# Power.net
KiCad netlist of a schematic drawn in Altium Designer
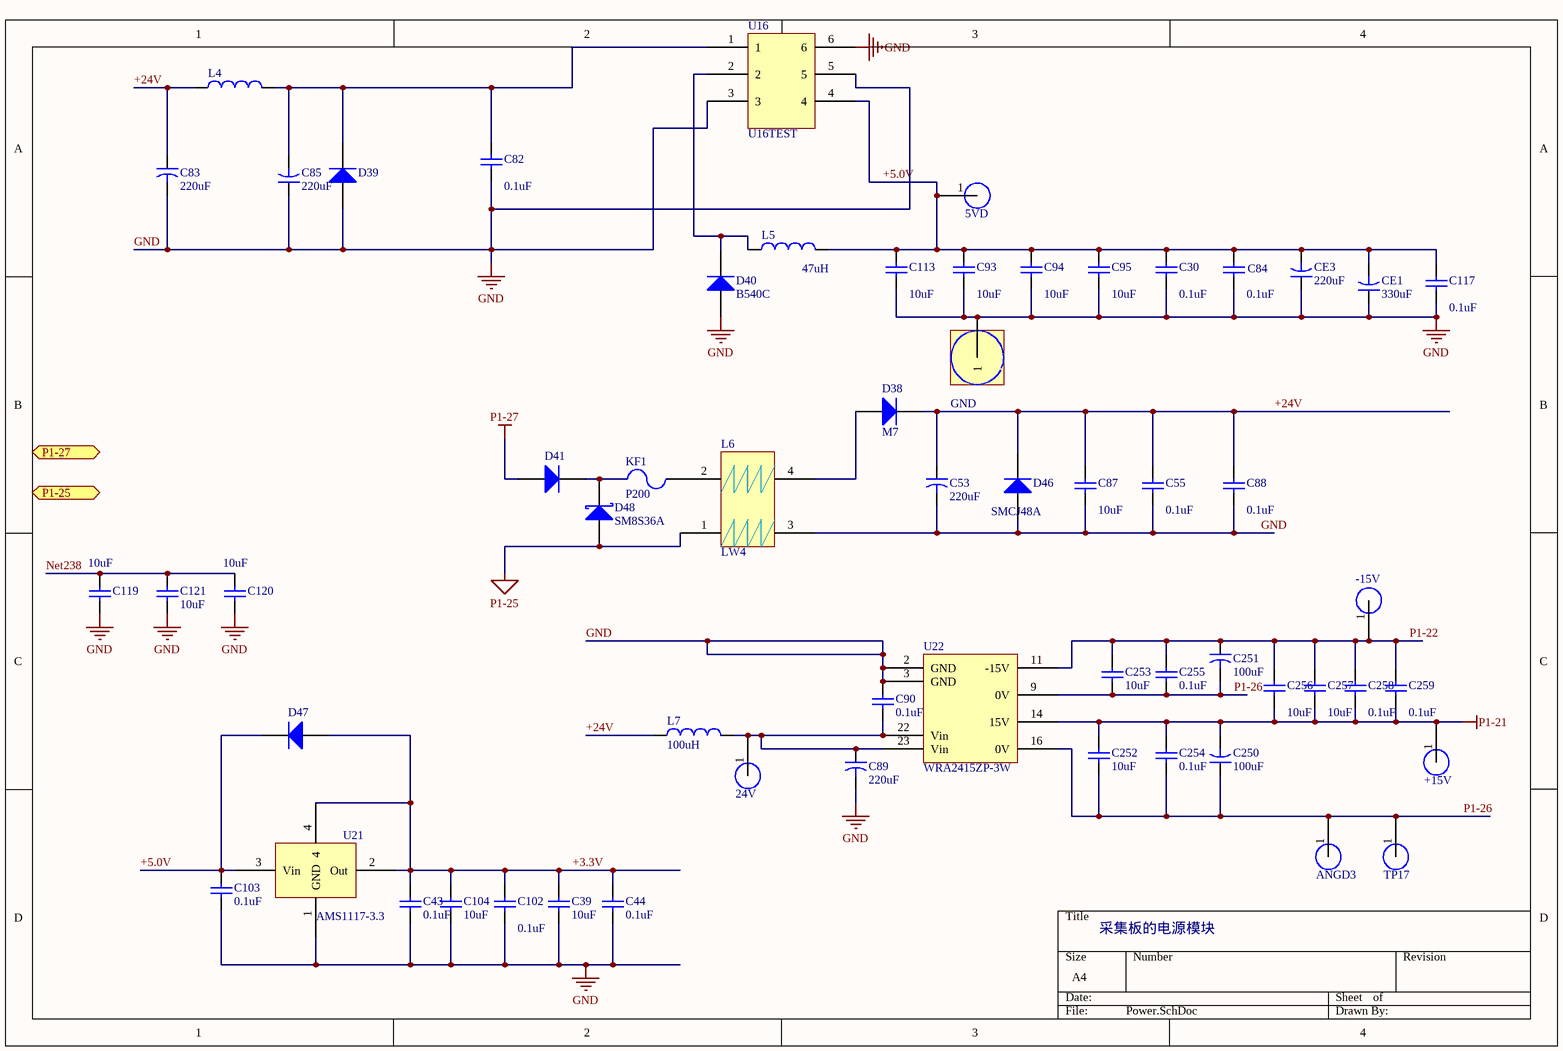
[diagram p0: Power.SchDoc]

(export (version "E")
  (design (tool "Eeschema 10.0.6"))
  (components
    (comp (ref "+15V") (value "PIN") (footprint "圆形焊盘") (libsource (lib "圆孔") (part "Component_1")))
    (comp (ref "-15V") (value "PIN") (footprint "圆形焊盘") (libsource (lib "圆孔") (part "Component_1")))
    (comp (ref "5VD") (value "PIN") (footprint "圆形焊盘") (libsource (lib "") (part "Component_1_1")))
    (comp (ref "24V") (value "PIN") (footprint "圆形焊盘") (libsource (lib "圆孔") (part "Component_1")))
    (comp (ref "ANGD3") (value "PIN") (footprint "圆形焊盘") (libsource (lib "圆孔") (part "Component_1")))
    (comp (ref "C30")
      (value "0.1uF")
      (footprint "采集板3.0增加1路模拟量2:C0805")
      (description "Capacitor")
      (fields (field (name "Comment") "104/10%") (field (name "PUBLISHER") "Altium Limited"))
      (libsource (lib "Miscellaneous Devices") (part "Cap"))
    )
    (comp (ref "C39")
      (value "10uF")
      (footprint "C1206")
      (description "Capacitor")
      (fields (field (name "Comment") "Cap") (field (name "PUBLISHER") "Altium Limited"))
      (libsource (lib "Miscellaneous Devices") (part "Cap"))
    )
    (comp (ref "C43")
      (value "0.1uF")
      (footprint "采集板3.0增加1路模拟量2:C0805")
      (description "Capacitor")
      (fields (field (name "Comment") "104/10%") (field (name "PUBLISHER") "Altium Limited"))
      (libsource (lib "Miscellaneous Devices") (part "Cap"))
    )
    (comp (ref "C44")
      (value "0.1uF")
      (footprint "采集板3.0增加1路模拟量2:C0805")
      (description "Capacitor")
      (fields (field (name "Comment") "Cap") (field (name "PUBLISHER") "Altium Limited"))
      (libsource (lib "Miscellaneous Devices") (part "Cap"))
    )
    (comp (ref "C53")
      (value "220uF")
      (footprint "采集板3.0增加1路模拟量2:8*12")
      (description "Capacitor")
      (fields (field (name "Comment") "Cap2") (field (name "PUBLISHER") "Altium Limited"))
      (libsource (lib "") (part "Cap2_1"))
    )
    (comp (ref "C55")
      (value "0.1uF")
      (footprint "采集板3.0增加1路模拟量2:C0805")
      (description "Capacitor")
      (fields (field (name "Comment") "104/10%") (field (name "PUBLISHER") "Altium Limited"))
      (libsource (lib "Miscellaneous Devices") (part "Cap"))
    )
    (comp (ref "C82")
      (value "0.1uF")
      (footprint "采集板3.0增加1路模拟量2:C0805")
      (description "Capacitor")
      (fields (field (name "Comment") "22pF/5%") (field (name "PUBLISHER") "Altium Limited"))
      (libsource (lib "Miscellaneous Devices") (part "Cap"))
    )
    (comp (ref "C83")
      (value "220uF")
      (footprint "采集板3.0增加1路模拟量2:8*12")
      (description "Capacitor")
      (fields (field (name "Comment") "Cap2") (field (name "PUBLISHER") "Altium Limited"))
      (libsource (lib "") (part "Cap2_1"))
    )
    (comp (ref "C84")
      (value "0.1uF")
      (footprint "采集板3.0增加1路模拟量2:C0805")
      (description "Capacitor")
      (fields (field (name "Comment") "104/10%") (field (name "PUBLISHER") "Altium Limited"))
      (libsource (lib "Miscellaneous Devices") (part "Cap"))
    )
    (comp (ref "C85")
      (value "220uF")
      (footprint "采集板3.0增加1路模拟量2:8*12")
      (description "Capacitor")
      (fields (field (name "Comment") "Cap2") (field (name "PUBLISHER") "Altium Limited"))
      (libsource (lib "Miscellaneous Devices") (part "Cap2"))
    )
    (comp (ref "C87")
      (value "10uF")
      (footprint "C1206")
      (description "Capacitor")
      (fields (field (name "PUBLISHER") "Altium Limited"))
      (libsource (lib "Miscellaneous Devices") (part "Cap"))
    )
    (comp (ref "C88")
      (value "0.1uF")
      (footprint "采集板3.0增加1路模拟量2:C0805")
      (description "Capacitor")
      (fields (field (name "Comment") "104/10%") (field (name "PUBLISHER") "Altium Limited"))
      (libsource (lib "Miscellaneous Devices") (part "Cap"))
    )
    (comp (ref "C89")
      (value "220uF")
      (footprint "采集板3.0增加1路模拟量2:8*12")
      (description "Capacitor")
      (fields (field (name "Comment") "Cap2") (field (name "PUBLISHER") "Altium Limited"))
      (libsource (lib "") (part "Cap2_1"))
    )
    (comp (ref "C90")
      (value "0.1uF")
      (footprint "采集板3.0增加1路模拟量2:C0805")
      (description "Capacitor")
      (fields (field (name "Comment") "104/10%") (field (name "PUBLISHER") "Altium Limited"))
      (libsource (lib "Miscellaneous Devices") (part "Cap"))
    )
    (comp (ref "C93")
      (value "10uF")
      (footprint "C1206")
      (description "Capacitor")
      (fields (field (name "PUBLISHER") "Altium Limited"))
      (libsource (lib "Miscellaneous Devices") (part "Cap"))
    )
    (comp (ref "C94")
      (value "10uF")
      (footprint "C1206")
      (description "Capacitor")
      (fields (field (name "PUBLISHER") "Altium Limited"))
      (libsource (lib "Miscellaneous Devices") (part "Cap"))
    )
    (comp (ref "C95")
      (value "10uF")
      (footprint "C1206")
      (description "Capacitor")
      (fields (field (name "PUBLISHER") "Altium Limited"))
      (libsource (lib "Miscellaneous Devices") (part "Cap"))
    )
    (comp (ref "C102")
      (value "0.1uF")
      (footprint "采集板3.0增加1路模拟量2:C0805")
      (description "Capacitor")
      (fields (field (name "Comment") "Cap") (field (name "PUBLISHER") "Altium Limited"))
      (libsource (lib "Miscellaneous Devices") (part "Cap"))
    )
    (comp (ref "C103")
      (value "0.1uF")
      (footprint "采集板3.0增加1路模拟量2:C0805")
      (description "Capacitor")
      (fields (field (name "Comment") "104/10%") (field (name "PUBLISHER") "Altium Limited"))
      (libsource (lib "Miscellaneous Devices") (part "Cap"))
    )
    (comp (ref "C104")
      (value "10uF")
      (footprint "C1206")
      (description "Capacitor")
      (fields (field (name "Comment") "Cap") (field (name "PUBLISHER") "Altium Limited"))
      (libsource (lib "Miscellaneous Devices") (part "Cap"))
    )
    (comp (ref "C113")
      (value "10uF")
      (footprint "C1206")
      (description "Capacitor")
      (fields (field (name "Comment") "Cap") (field (name "PUBLISHER") "Altium Limited"))
      (libsource (lib "Miscellaneous Devices") (part "Cap"))
    )
    (comp (ref "C117")
      (value "0.1uF")
      (footprint "采集板3.0增加1路模拟量2:C0805")
      (description "Capacitor")
      (fields (field (name "Comment") "Cap") (field (name "PUBLISHER") "Altium Limited"))
      (libsource (lib "Miscellaneous Devices") (part "Cap"))
    )
    (comp (ref "C119")
      (value "10uF")
      (footprint "C1210")
      (description "Capacitor")
      (fields (field (name "Comment") "Cap") (field (name "PUBLISHER") "Altium Limited"))
      (libsource (lib "Miscellaneous Devices") (part "Cap"))
    )
    (comp (ref "C120")
      (value "10uF")
      (footprint "C1210")
      (description "Capacitor")
      (fields (field (name "Comment") "Cap") (field (name "PUBLISHER") "Altium Limited"))
      (libsource (lib "Miscellaneous Devices") (part "Cap"))
    )
    (comp (ref "C121")
      (value "10uF")
      (footprint "C1210")
      (description "Capacitor")
      (fields (field (name "Comment") "Cap") (field (name "PUBLISHER") "Altium Limited"))
      (libsource (lib "Miscellaneous Devices") (part "Cap"))
    )
    (comp (ref "C250")
      (value "100uF")
      (footprint "采集板3.0增加1路模拟量2:8*12")
      (description "Capacitor")
      (fields (field (name "Comment") "Cap2") (field (name "PUBLISHER") "Altium Limited"))
      (libsource (lib "Miscellaneous Devices") (part "Cap2"))
    )
    (comp (ref "C251")
      (value "100uF")
      (footprint "采集板3.0增加1路模拟量2:8*12")
      (description "Capacitor")
      (fields (field (name "Comment") "Cap2") (field (name "PUBLISHER") "Altium Limited"))
      (libsource (lib "Miscellaneous Devices") (part "Cap2"))
    )
    (comp (ref "C252")
      (value "10uF")
      (footprint "C1206")
      (description "Capacitor")
      (fields (field (name "PUBLISHER") "Altium Limited"))
      (libsource (lib "Miscellaneous Devices") (part "Cap"))
    )
    (comp (ref "C253")
      (value "10uF")
      (footprint "C1206")
      (description "Capacitor")
      (fields (field (name "PUBLISHER") "Altium Limited"))
      (libsource (lib "Miscellaneous Devices") (part "Cap"))
    )
    (comp (ref "C254")
      (value "0.1uF")
      (footprint "采集板3.0增加1路模拟量2:C0805")
      (description "Capacitor")
      (fields (field (name "Comment") "104/10%") (field (name "PUBLISHER") "Altium Limited"))
      (libsource (lib "Miscellaneous Devices") (part "Cap"))
    )
    (comp (ref "C255")
      (value "0.1uF")
      (footprint "采集板3.0增加1路模拟量2:C0805")
      (description "Capacitor")
      (fields (field (name "Comment") "104/10%") (field (name "PUBLISHER") "Altium Limited"))
      (libsource (lib "Miscellaneous Devices") (part "Cap"))
    )
    (comp (ref "C256")
      (value "10uF")
      (footprint "C1206")
      (description "Capacitor")
      (fields (field (name "PUBLISHER") "Altium Limited"))
      (libsource (lib "Miscellaneous Devices") (part "Cap"))
    )
    (comp (ref "C257")
      (value "10uF")
      (footprint "C1206")
      (description "Capacitor")
      (fields (field (name "PUBLISHER") "Altium Limited"))
      (libsource (lib "Miscellaneous Devices") (part "Cap"))
    )
    (comp (ref "C258")
      (value "0.1uF")
      (footprint "采集板3.0增加1路模拟量2:C0805")
      (description "Capacitor")
      (fields (field (name "Comment") "104/10%") (field (name "PUBLISHER") "Altium Limited"))
      (libsource (lib "Miscellaneous Devices") (part "Cap"))
    )
    (comp (ref "C259")
      (value "0.1uF")
      (footprint "采集板3.0增加1路模拟量2:C0805")
      (description "Capacitor")
      (fields (field (name "Comment") "104/10%") (field (name "PUBLISHER") "Altium Limited"))
      (libsource (lib "Miscellaneous Devices") (part "Cap"))
    )
    (comp (ref "CE1")
      (value "330uF")
      (footprint "采集板3.0增加1路模拟量2:8*12")
      (description "Capacitor")
      (fields (field (name "Comment") "Cap2") (field (name "PUBLISHER") "Altium Limited"))
      (libsource (lib "Miscellaneous Devices") (part "Cap2"))
    )
    (comp (ref "CE3")
      (value "220uF")
      (footprint "采集板3.0增加1路模拟量2:8*12")
      (description "Capacitor")
      (fields (field (name "Comment") "Cap2") (field (name "PUBLISHER") "Altium Limited"))
      (libsource (lib "Miscellaneous Devices") (part "Cap2"))
    )
    (comp (ref "D38")
      (value "M7")
      (footprint "DO214AB")
      (description "1 Amp General Purpose Rectifier")
      (fields (field (name "PUBLISHER") "Altium Limited"))
      (libsource (lib "Miscellaneous Devices") (part "Diode 1N4007"))
    )
    (comp (ref "D39")
      (value "SMCJ48A")
      (footprint "DO214AB")
      (description "Default Diode")
      (fields (field (name "PUBLISHER") "Altium Limited"))
      (libsource (lib "Miscellaneous Devices") (part "Diode"))
    )
    (comp (ref "D40")
      (value "B540C")
      (footprint "DO214AB")
      (description "1 Amp General Purpose Rectifier")
      (fields (field (name "PUBLISHER") "Altium Limited"))
      (libsource (lib "Miscellaneous Devices") (part "Diode 1N4007"))
    )
    (comp (ref "D41")
      (value "B540C")
      (footprint "DO214AB")
      (description "1 Amp General Purpose Rectifier")
      (fields (field (name "PUBLISHER") "Altium Limited"))
      (libsource (lib "Miscellaneous Devices") (part "Diode 1N4007"))
    )
    (comp (ref "D46")
      (value "SMCJ48A")
      (footprint "DO214AB")
      (description "Default Diode")
      (fields (field (name "PUBLISHER") "Altium Limited"))
      (libsource (lib "Miscellaneous Devices") (part "Diode"))
    )
    (comp (ref "D47")
      (value "Diode 1N4007")
      (footprint "SOD123")
      (description "1 Amp General Purpose Rectifier")
      (fields (field (name "PUBLISHER") "Altium Limited"))
      (libsource (lib "Miscellaneous Devices") (part "Diode 1N4007"))
    )
    (comp (ref "D48")
      (value "SM8S36A")
      (footprint "采集板3.0增加1路模拟量2:DO-218AB")
      (description "Schottky Diode")
      (fields (field (name "PUBLISHER") "Altium Limited"))
      (libsource (lib "Miscellaneous Devices") (part "D Schottky"))
    )
    (comp (ref "GND") (value "TEST") (footprint "方形焊盘") (libsource (lib "方孔") (part "Component_1")))
    (comp (ref "KF1")
      (value "P200")
      (footprint "1812")
      (description "Fuse")
      (fields (field (name "PUBLISHER") "Altium Limited"))
      (libsource (lib "Miscellaneous Devices") (part "Fuse 2"))
    )
    (comp (ref "L4")
      (value "101")
      (footprint "7*7")
      (description "Inductor")
      (fields (field (name "PUBLISHER") "Altium Limited"))
      (libsource (lib "Miscellaneous Devices") (part "Inductor"))
    )
    (comp (ref "L5")
      (value "47uH")
      (footprint "12.5*12.5")
      (description "Inductor")
      (fields (field (name "Comment") "SLF12575T-470M2R7-PF") (field (name "PUBLISHER") "Altium Limited"))
      (libsource (lib "Miscellaneous Devices") (part "Inductor"))
    )
    (comp (ref "L6") (value "LW4") (footprint "直插共模电感") (libsource (lib "L4") (part "LW4")))
    (comp (ref "L7")
      (value "100uH")
      (footprint "7*7")
      (description "Inductor")
      (fields (field (name "Comment") "101") (field (name "PUBLISHER") "Altium Limited"))
      (libsource (lib "Miscellaneous Devices") (part "Inductor"))
    )
    (comp (ref "TP17") (value "PIN") (footprint "圆形焊盘") (libsource (lib "圆孔") (part "Component_1")))
    (comp (ref "U16")
      (value "U16TEST")
      (footprint "采集板3.0增加1路模拟量2:TOP2-63")
      (libsource (lib "Schlib1") (part "Component_1"))
    )
    (comp (ref "U21")
      (value "AMS1117-3.3")
      (footprint "SOT-223")
      (libsource (lib "AMS1117-3.3") (part "Component_1"))
    )
    (comp (ref "U22")
      (value "WRA2415ZP-3W")
      (footprint "WRA2415")
      (libsource (lib "war2415zp3wr") (part "WRA2415ZP-3W"))
    )
  )
  (nets
    (net (code "1") (name "/+3.3V") (class "Default")
      (node (ref "C102") (pin "2") (pinfunction "2_2") (pintype "passive"))
      (node (ref "C104") (pin "1") (pinfunction "1_1") (pintype "passive"))
      (node (ref "C39") (pin "1") (pinfunction "1_1") (pintype "passive"))
      (node (ref "C43") (pin "2") (pinfunction "2_2") (pintype "passive"))
      (node (ref "C44") (pin "1") (pinfunction "1_1") (pintype "passive"))
      (node (ref "D47") (pin "1") (pinfunction "A_1") (pintype "passive"))
      (node (ref "U21") (pin "2") (pinfunction "Out_2") (pintype "passive"))
      (node (ref "U21") (pin "4") (pinfunction "4_4") (pintype "passive"))
    )
    (net (code "2") (name "/+5.0V") (class "Default")
      (node (ref "5VD") (pin "1") (pinfunction "1_1") (pintype "passive"))
      (node (ref "C103") (pin "1") (pinfunction "1_1") (pintype "passive"))
      (node (ref "C113") (pin "2") (pinfunction "2_2") (pintype "passive"))
      (node (ref "C117") (pin "2") (pinfunction "2_2") (pintype "passive"))
      (node (ref "C30") (pin "1") (pinfunction "1_1") (pintype "passive"))
      (node (ref "C84") (pin "1") (pinfunction "1_1") (pintype "passive"))
      (node (ref "C93") (pin "1") (pinfunction "1_1") (pintype "passive"))
      (node (ref "C94") (pin "1") (pinfunction "1_1") (pintype "passive"))
      (node (ref "C95") (pin "1") (pinfunction "1_1") (pintype "passive"))
      (node (ref "CE1") (pin "2") (pinfunction "2_2") (pintype "passive"))
      (node (ref "CE3") (pin "2") (pinfunction "2_2") (pintype "passive"))
      (node (ref "D47") (pin "2") (pinfunction "K_2") (pintype "passive"))
      (node (ref "L5") (pin "2") (pinfunction "2_2") (pintype "passive"))
      (node (ref "U16") (pin "4") (pinfunction "4_4") (pintype "passive"))
      (node (ref "U21") (pin "3") (pinfunction "Vin_3") (pintype "passive"))
    )
    (net (code "3") (name "/+24V") (class "Default")
      (node (ref "C53") (pin "2") (pinfunction "2_2") (pintype "passive"))
      (node (ref "C55") (pin "2") (pinfunction "2_2") (pintype "passive"))
      (node (ref "C83") (pin "2") (pinfunction "2_2") (pintype "passive"))
      (node (ref "C87") (pin "2") (pinfunction "2_2") (pintype "passive"))
      (node (ref "C88") (pin "2") (pinfunction "2_2") (pintype "passive"))
      (node (ref "D38") (pin "2") (pinfunction "K_2") (pintype "passive"))
      (node (ref "D46") (pin "2") (pinfunction "K_2") (pintype "passive"))
      (node (ref "L4") (pin "1") (pinfunction "1_1") (pintype "passive"))
      (node (ref "L7") (pin "1") (pinfunction "1_1") (pintype "passive"))
    )
    (net (code "4") (name "/Net238") (class "Default")
      (node (ref "C119") (pin "1") (pinfunction "1_1") (pintype "passive"))
      (node (ref "C120") (pin "1") (pinfunction "1_1") (pintype "passive"))
      (node (ref "C121") (pin "2") (pinfunction "2_2") (pintype "passive"))
    )
    (net (code "5") (name "/P1-22") (class "Default")
      (node (ref "-15V") (pin "1") (pinfunction "1_1") (pintype "passive"))
      (node (ref "C251") (pin "1") (pinfunction "1_1") (pintype "passive"))
      (node (ref "C253") (pin "1") (pinfunction "1_1") (pintype "passive"))
      (node (ref "C255") (pin "1") (pinfunction "1_1") (pintype "passive"))
      (node (ref "C256") (pin "2") (pinfunction "2_2") (pintype "passive"))
      (node (ref "C257") (pin "2") (pinfunction "2_2") (pintype "passive"))
      (node (ref "C258") (pin "2") (pinfunction "2_2") (pintype "passive"))
      (node (ref "C259") (pin "2") (pinfunction "2_2") (pintype "passive"))
      (node (ref "U22") (pin "11") (pinfunction "-15V_11") (pintype "passive"))
    )
    (net (code "6") (name "/P1-26") (class "Default")
      (node (ref "ANGD3") (pin "1") (pinfunction "1_1") (pintype "passive"))
      (node (ref "C250") (pin "1") (pinfunction "1_1") (pintype "passive"))
      (node (ref "C251") (pin "2") (pinfunction "2_2") (pintype "passive"))
      (node (ref "C252") (pin "2") (pinfunction "2_2") (pintype "passive"))
      (node (ref "C253") (pin "2") (pinfunction "2_2") (pintype "passive"))
      (node (ref "C254") (pin "2") (pinfunction "2_2") (pintype "passive"))
      (node (ref "C255") (pin "2") (pinfunction "2_2") (pintype "passive"))
      (node (ref "TP17") (pin "1") (pinfunction "1_1") (pintype "passive"))
      (node (ref "U22") (pin "16") (pinfunction "0V_16") (pintype "passive"))
      (node (ref "U22") (pin "9") (pinfunction "0V_9") (pintype "passive"))
    )
    (net (code "7") (name "GND") (class "Default")
      (node (ref "C102") (pin "1") (pinfunction "1_1") (pintype "passive"))
      (node (ref "C103") (pin "2") (pinfunction "2_2") (pintype "passive"))
      (node (ref "C104") (pin "2") (pinfunction "2_2") (pintype "passive"))
      (node (ref "C113") (pin "1") (pinfunction "1_1") (pintype "passive"))
      (node (ref "C117") (pin "1") (pinfunction "1_1") (pintype "passive"))
      (node (ref "C119") (pin "2") (pinfunction "2_2") (pintype "passive"))
      (node (ref "C120") (pin "2") (pinfunction "2_2") (pintype "passive"))
      (node (ref "C121") (pin "1") (pinfunction "1_1") (pintype "passive"))
      (node (ref "C30") (pin "2") (pinfunction "2_2") (pintype "passive"))
      (node (ref "C39") (pin "2") (pinfunction "2_2") (pintype "passive"))
      (node (ref "C43") (pin "1") (pinfunction "1_1") (pintype "passive"))
      (node (ref "C44") (pin "2") (pinfunction "2_2") (pintype "passive"))
      (node (ref "C53") (pin "1") (pinfunction "1_1") (pintype "passive"))
      (node (ref "C55") (pin "1") (pinfunction "1_1") (pintype "passive"))
      (node (ref "C82") (pin "1") (pinfunction "1_1") (pintype "passive"))
      (node (ref "C83") (pin "1") (pinfunction "1_1") (pintype "passive"))
      (node (ref "C84") (pin "2") (pinfunction "2_2") (pintype "passive"))
      (node (ref "C85") (pin "1") (pinfunction "1_1") (pintype "passive"))
      (node (ref "C87") (pin "1") (pinfunction "1_1") (pintype "passive"))
      (node (ref "C88") (pin "1") (pinfunction "1_1") (pintype "passive"))
      (node (ref "C89") (pin "1") (pinfunction "1_1") (pintype "passive"))
      (node (ref "C90") (pin "1") (pinfunction "1_1") (pintype "passive"))
      (node (ref "C93") (pin "2") (pinfunction "2_2") (pintype "passive"))
      (node (ref "C94") (pin "2") (pinfunction "2_2") (pintype "passive"))
      (node (ref "C95") (pin "2") (pinfunction "2_2") (pintype "passive"))
      (node (ref "CE1") (pin "1") (pinfunction "1_1") (pintype "passive"))
      (node (ref "CE3") (pin "1") (pinfunction "1_1") (pintype "passive"))
      (node (ref "D39") (pin "1") (pinfunction "A_1") (pintype "passive"))
      (node (ref "D40") (pin "1") (pinfunction "A_1") (pintype "passive"))
      (node (ref "D46") (pin "1") (pinfunction "A_1") (pintype "passive"))
      (node (ref "GND") (pin "1") (pinfunction "1_1") (pintype "passive"))
      (node (ref "L6") (pin "3") (pinfunction "3_3") (pintype "passive"))
      (node (ref "U16") (pin "3") (pinfunction "3_3") (pintype "passive"))
      (node (ref "U16") (pin "5") (pinfunction "5_5") (pintype "passive"))
      (node (ref "U16") (pin "6") (pinfunction "6_6") (pintype "passive"))
      (node (ref "U21") (pin "1") (pinfunction "GND_1") (pintype "passive"))
      (node (ref "U22") (pin "2") (pinfunction "GND_2") (pintype "passive"))
      (node (ref "U22") (pin "3") (pinfunction "GND_3") (pintype "passive"))
    )
    (net (code "8") (name "Net-(24V-Pad1)") (class "Default")
      (node (ref "24V") (pin "1") (pinfunction "1_1") (pintype "passive"))
      (node (ref "C89") (pin "2") (pinfunction "2_2") (pintype "passive"))
      (node (ref "C90") (pin "2") (pinfunction "2_2") (pintype "passive"))
      (node (ref "L7") (pin "2") (pinfunction "2_2") (pintype "passive"))
      (node (ref "U22") (pin "22") (pinfunction "Vin_22") (pintype "passive"))
      (node (ref "U22") (pin "23") (pinfunction "Vin_23") (pintype "passive"))
    )
    (net (code "9") (name "Net-(D38-A)") (class "Default")
      (node (ref "D38") (pin "1") (pinfunction "A_1") (pintype "passive"))
      (node (ref "L6") (pin "4") (pinfunction "4_4") (pintype "passive"))
    )
    (net (code "10") (name "Net-(D39-K)") (class "Default")
      (node (ref "C82") (pin "2") (pinfunction "2_2") (pintype "passive"))
      (node (ref "C85") (pin "2") (pinfunction "2_2") (pintype "passive"))
      (node (ref "D39") (pin "2") (pinfunction "K_2") (pintype "passive"))
      (node (ref "L4") (pin "2") (pinfunction "2_2") (pintype "passive"))
      (node (ref "U16") (pin "1") (pinfunction "1_1") (pintype "passive"))
    )
    (net (code "11") (name "Net-(D40-K)") (class "Default")
      (node (ref "D40") (pin "2") (pinfunction "K_2") (pintype "passive"))
      (node (ref "L5") (pin "1") (pinfunction "1_1") (pintype "passive"))
      (node (ref "U16") (pin "2") (pinfunction "2_2") (pintype "passive"))
    )
    (net (code "12") (name "Net-(D41-K)") (class "Default")
      (node (ref "D41") (pin "2") (pinfunction "K_2") (pintype "passive"))
      (node (ref "D48") (pin "1") (pinfunction "K_1") (pintype "passive"))
      (node (ref "KF1") (pin "2") (pinfunction "2_2") (pintype "passive"))
    )
    (net (code "13") (name "Net-(KF1-Pad1)") (class "Default")
      (node (ref "KF1") (pin "1") (pinfunction "1_1") (pintype "passive"))
      (node (ref "L6") (pin "2") (pinfunction "2_2") (pintype "passive"))
    )
    (net (code "14") (name "P1-21") (class "Default")
      (node (ref "+15V") (pin "1") (pinfunction "1_1") (pintype "passive"))
      (node (ref "C250") (pin "2") (pinfunction "2_2") (pintype "passive"))
      (node (ref "C252") (pin "1") (pinfunction "1_1") (pintype "passive"))
      (node (ref "C254") (pin "1") (pinfunction "1_1") (pintype "passive"))
      (node (ref "C256") (pin "1") (pinfunction "1_1") (pintype "passive"))
      (node (ref "C257") (pin "1") (pinfunction "1_1") (pintype "passive"))
      (node (ref "C258") (pin "1") (pinfunction "1_1") (pintype "passive"))
      (node (ref "C259") (pin "1") (pinfunction "1_1") (pintype "passive"))
      (node (ref "U22") (pin "14") (pinfunction "15V_14") (pintype "passive"))
    )
    (net (code "15") (name "P1-25") (class "Default")
      (node (ref "D48") (pin "2") (pinfunction "A_2") (pintype "passive"))
      (node (ref "L6") (pin "1") (pinfunction "1_1") (pintype "passive"))
    )
    (net (code "16") (name "P1-27") (class "Default")
      (node (ref "D41") (pin "1") (pinfunction "A_1") (pintype "passive"))
    )
  )
)
